# Zigbee.net
KiCad netlist of a schematic drawn in Altium Designer
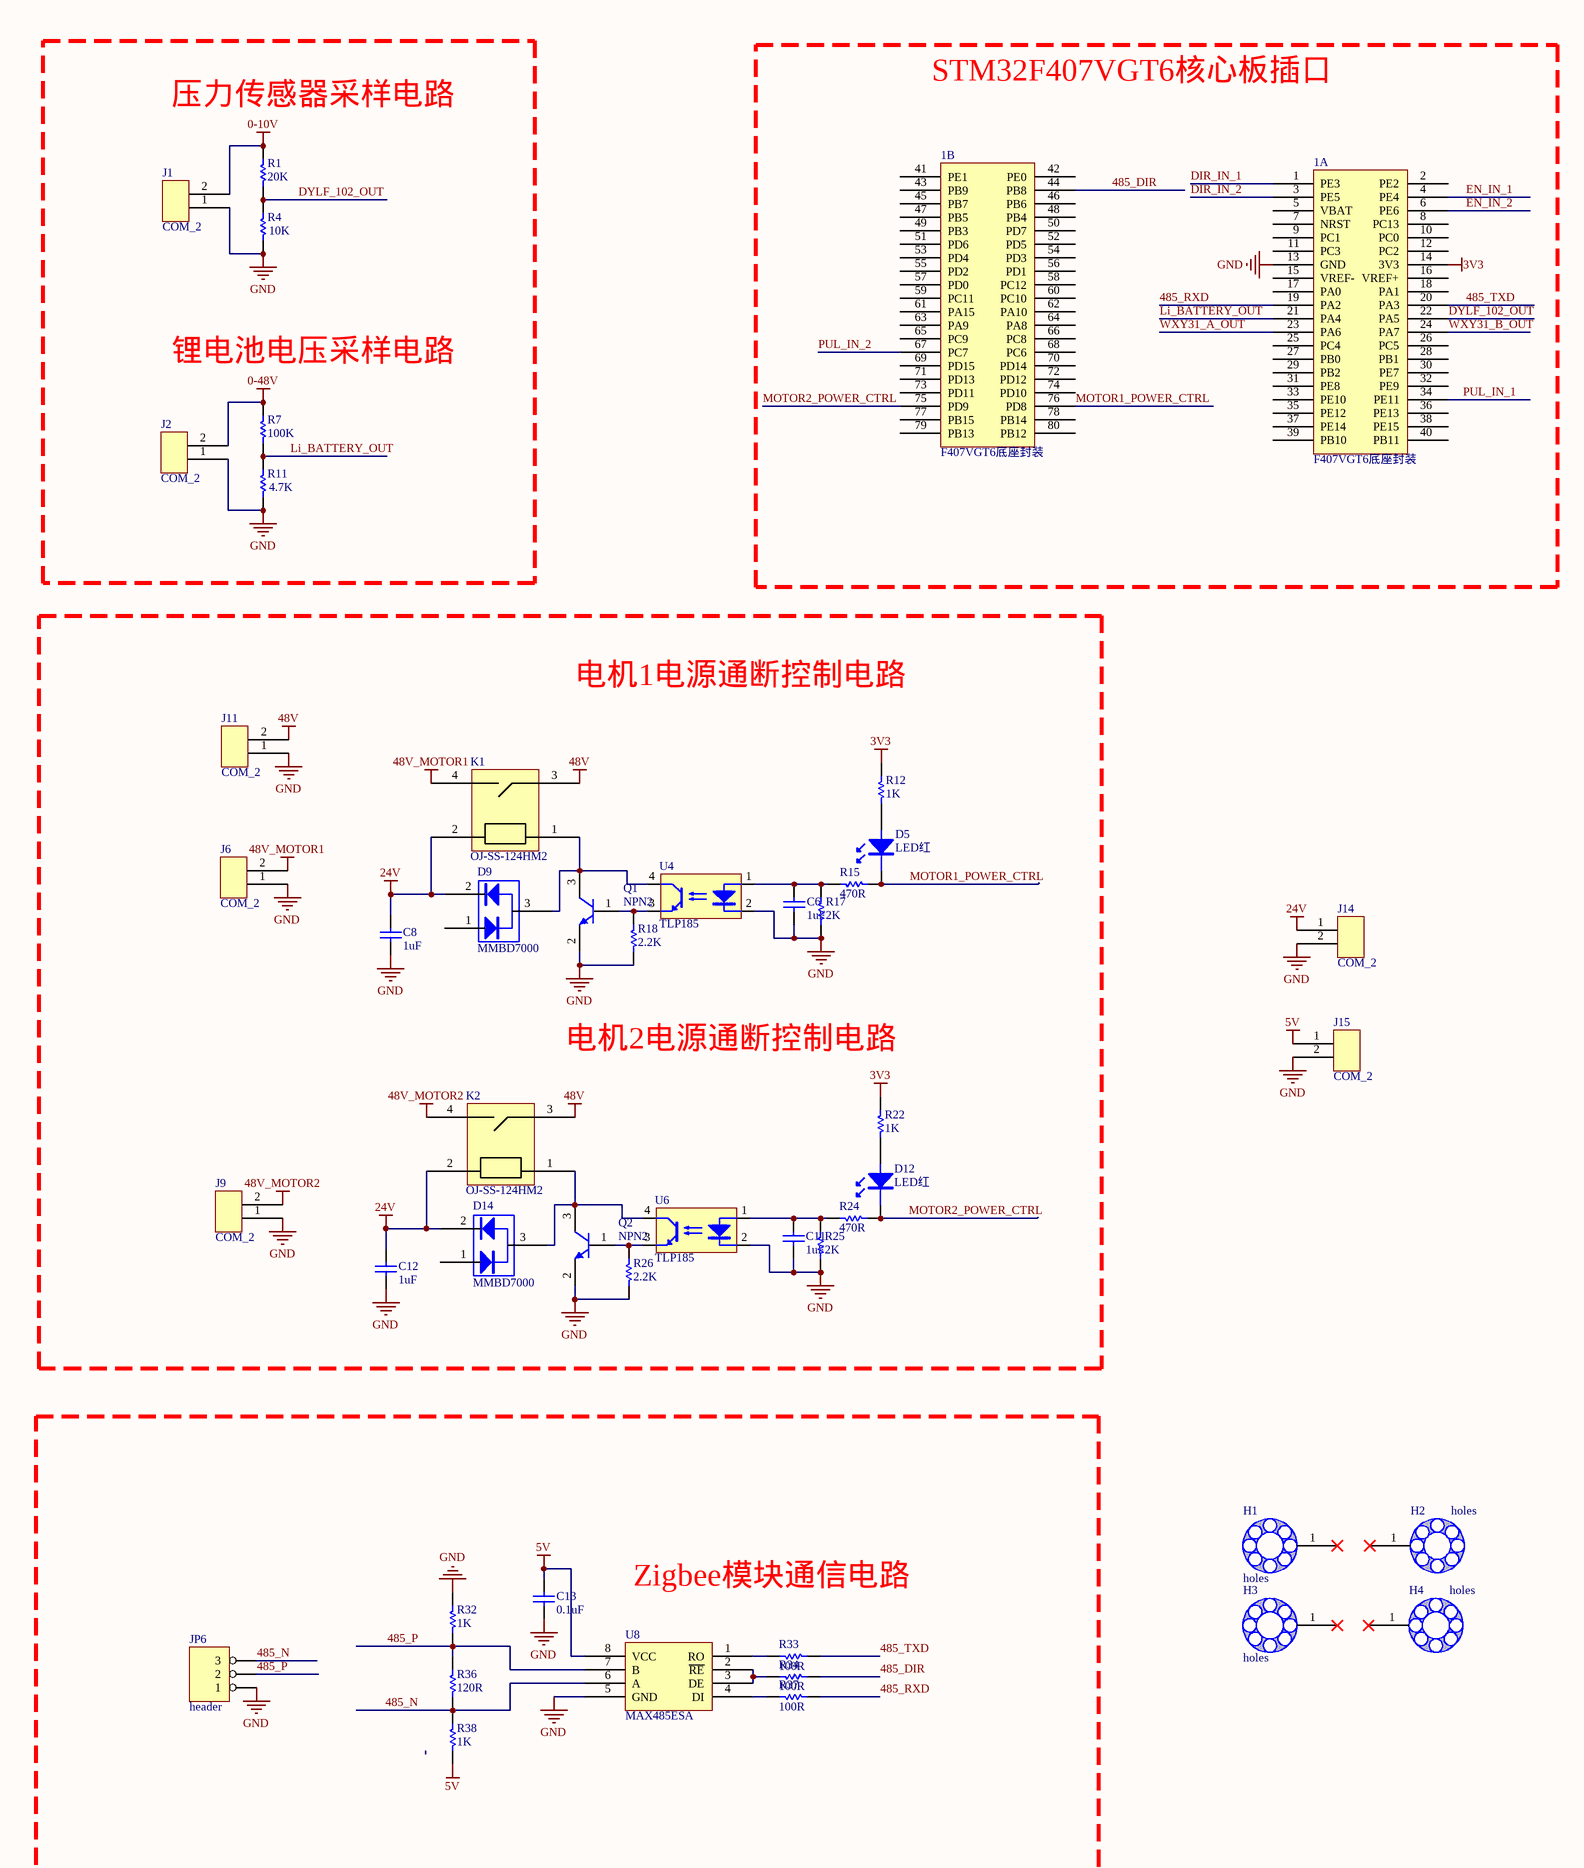
[diagram p0: Zigbee.SchDoc, left]
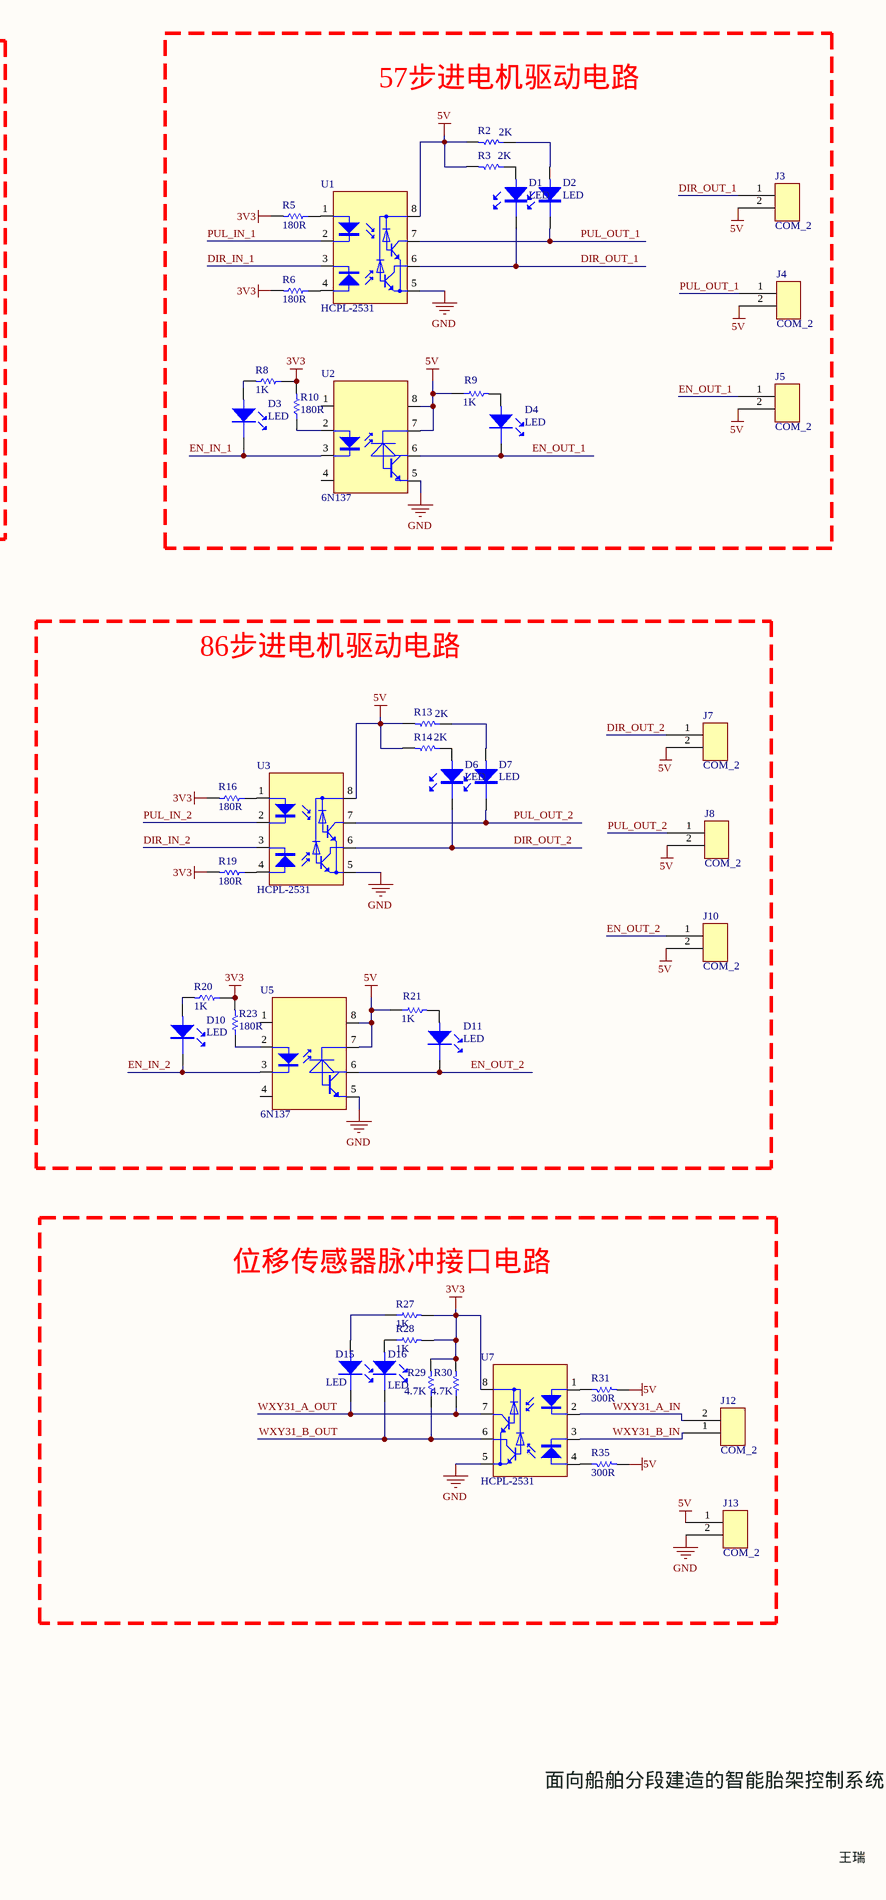
[diagram p1: Zigbee.SchDoc, right]

(export (version "E")
  (design (tool "Eeschema 10.0.6"))
  (components
    (comp (ref "1")
      (value "F407VGT6底座封装")
      (footprint "F407VGT6底座封装")
      (libsource (lib "F407VGT6底座封装") (part "F407VGT6底座封装"))
    )
    (comp (ref "C6")
      (value "1uF")
      (footprint "0603_C")
      (description "Capacitor")
      (fields (field (name "PUBLISHER") "Altium Limited"))
      (libsource (lib "My Footprint") (part "CAP"))
    )
    (comp (ref "C8")
      (value "1uF")
      (footprint "0603_C")
      (description "Capacitor")
      (fields (field (name "PUBLISHER") "Altium Limited"))
      (libsource (lib "My Footprint") (part "CAP"))
    )
    (comp (ref "C11")
      (value "1uF")
      (footprint "0603_C")
      (description "Capacitor")
      (fields (field (name "PUBLISHER") "Altium Limited"))
      (libsource (lib "My Footprint") (part "CAP"))
    )
    (comp (ref "C12")
      (value "1uF")
      (footprint "0603_C")
      (description "Capacitor")
      (fields (field (name "PUBLISHER") "Altium Limited"))
      (libsource (lib "My Footprint") (part "CAP"))
    )
    (comp (ref "C13")
      (value "0.1uF")
      (footprint "0603_C")
      (description "Capacitor")
      (fields (field (name "PUBLISHER") "Altium Limited"))
      (libsource (lib "My Footprint") (part "CAP"))
    )
    (comp (ref "D1")
      (value "LED")
      (footprint "0603_LED")
      (description "LED 发光二极管")
      (libsource (lib "My Footprint") (part "LED"))
    )
    (comp (ref "D2")
      (value "LED")
      (footprint "0603_LED")
      (description "LED 发光二极管")
      (libsource (lib "My Footprint") (part "LED"))
    )
    (comp (ref "D3")
      (value "LED")
      (footprint "0603_LED")
      (description "LED 发光二极管")
      (libsource (lib "My Footprint") (part "LED"))
    )
    (comp (ref "D4")
      (value "LED")
      (footprint "0603_LED")
      (description "LED 发光二极管")
      (libsource (lib "My Footprint") (part "LED"))
    )
    (comp (ref "D5")
      (value "LED红")
      (footprint "0603_LED")
      (description "LED 发光二极管")
      (libsource (lib "My Footprint") (part "LED"))
    )
    (comp (ref "D6")
      (value "LED")
      (footprint "0603_LED")
      (description "LED 发光二极管")
      (libsource (lib "My Footprint") (part "LED"))
    )
    (comp (ref "D7")
      (value "LED")
      (footprint "0603_LED")
      (description "LED 发光二极管")
      (libsource (lib "My Footprint") (part "LED"))
    )
    (comp (ref "D9") (value "MMBD7000") (footprint "SOT23") (libsource (lib "Footprint") (part "MMBD7000")))
    (comp (ref "D10")
      (value "LED")
      (footprint "0603_LED")
      (description "LED 发光二极管")
      (libsource (lib "My Footprint") (part "LED"))
    )
    (comp (ref "D11")
      (value "LED")
      (footprint "0603_LED")
      (description "LED 发光二极管")
      (libsource (lib "My Footprint") (part "LED"))
    )
    (comp (ref "D12")
      (value "LED红")
      (footprint "0603_LED")
      (description "LED 发光二极管")
      (libsource (lib "My Footprint") (part "LED"))
    )
    (comp (ref "D14") (value "MMBD7000") (footprint "SOT23") (libsource (lib "Footprint") (part "MMBD7000")))
    (comp (ref "D15")
      (value "LED")
      (footprint "0603_LED")
      (description "LED 发光二极管")
      (libsource (lib "My Footprint") (part "LED"))
    )
    (comp (ref "D16")
      (value "LED")
      (footprint "0603_LED")
      (description "LED 发光二极管")
      (libsource (lib "My Footprint") (part "LED"))
    )
    (comp (ref "H1") (value "holes") (footprint "铜柱（小焊盘）") (libsource (lib "Footprint") (part "铜柱")))
    (comp (ref "H2") (value "holes") (footprint "铜柱（小焊盘）") (libsource (lib "Footprint") (part "铜柱")))
    (comp (ref "H3") (value "holes") (footprint "铜柱（小焊盘）") (libsource (lib "Footprint") (part "铜柱")))
    (comp (ref "H4") (value "holes") (footprint "铜柱（小焊盘）") (libsource (lib "Footprint") (part "铜柱")))
    (comp (ref "J1") (value "COM_2") (footprint "5.08A-2PIN") (libsource (lib "") (part "COM_2_1")))
    (comp (ref "J2") (value "COM_2") (footprint "5.08A-2PIN") (libsource (lib "") (part "COM_2_1")))
    (comp (ref "J3") (value "COM_2") (footprint "5.08A-2PIN") (libsource (lib "Footprint") (part "COM_2")))
    (comp (ref "J4") (value "COM_2") (footprint "5.08A-2PIN") (libsource (lib "Footprint") (part "COM_2")))
    (comp (ref "J5") (value "COM_2") (footprint "5.08A-2PIN") (libsource (lib "Footprint") (part "COM_2")))
    (comp (ref "J6") (value "COM_2") (footprint "5.08A-2PIN") (libsource (lib "") (part "COM_2_1")))
    (comp (ref "J7") (value "COM_2") (footprint "5.08A-2PIN") (libsource (lib "Footprint") (part "COM_2")))
    (comp (ref "J8") (value "COM_2") (footprint "5.08A-2PIN") (libsource (lib "Footprint") (part "COM_2")))
    (comp (ref "J9") (value "COM_2") (footprint "5.08A-2PIN") (libsource (lib "") (part "COM_2_1")))
    (comp (ref "J10") (value "COM_2") (footprint "5.08A-2PIN") (libsource (lib "Footprint") (part "COM_2")))
    (comp (ref "J11") (value "COM_2") (footprint "5.08A-2PIN") (libsource (lib "") (part "COM_2_1")))
    (comp (ref "J12") (value "COM_2") (footprint "5.08A-2PIN") (libsource (lib "") (part "COM_2_2")))
    (comp (ref "J13") (value "COM_2") (footprint "5.08A-2PIN") (libsource (lib "Footprint") (part "COM_2")))
    (comp (ref "J14") (value "COM_2") (footprint "5.08A-2PIN") (libsource (lib "Footprint") (part "COM_2")))
    (comp (ref "J15") (value "COM_2") (footprint "5.08A-2PIN") (libsource (lib "Footprint") (part "COM_2")))
    (comp (ref "JP6")
      (value "header")
      (footprint "5.08A-3PIN")
      (libsource (lib "My Footprint") (part "HEADER 3"))
    )
    (comp (ref "K1")
      (value "OJ-SS-124HM2")
      (footprint "G4A-1A-PE-24V")
      (libsource (lib "Footprint") (part "OJ-SS-124HM2"))
    )
    (comp (ref "K2")
      (value "OJ-SS-124HM2")
      (footprint "G4A-1A-PE-24V")
      (libsource (lib "Footprint") (part "OJ-SS-124HM2"))
    )
    (comp (ref "Q1")
      (value "NPN2")
      (footprint "SOT-23-3")
      (description "贴片")
      (libsource (lib "My Footprint") (part "NPN2"))
    )
    (comp (ref "Q2")
      (value "NPN2")
      (footprint "SOT-23-3")
      (description "贴片")
      (libsource (lib "My Footprint") (part "NPN2"))
    )
    (comp (ref "R1")
      (value "20K")
      (footprint "0603_R")
      (description "Resistor")
      (fields (field (name "PUBLISHER") "Altium Limited"))
      (libsource (lib "My Footprint") (part "RES"))
    )
    (comp (ref "R2")
      (value "2K")
      (footprint "0603_R")
      (description "Resistor")
      (fields (field (name "PUBLISHER") "Altium Limited"))
      (libsource (lib "My Footprint") (part "RES"))
    )
    (comp (ref "R3")
      (value "2K")
      (footprint "0603_R")
      (description "Resistor")
      (fields (field (name "PUBLISHER") "Altium Limited"))
      (libsource (lib "My Footprint") (part "RES"))
    )
    (comp (ref "R4")
      (value "10K")
      (footprint "0603_R")
      (description "Resistor")
      (fields (field (name "PUBLISHER") "Altium Limited"))
      (libsource (lib "My Footprint") (part "RES"))
    )
    (comp (ref "R5")
      (value "180R")
      (footprint "0603_R")
      (description "Resistor")
      (fields (field (name "PUBLISHER") "Altium Limited"))
      (libsource (lib "My Footprint") (part "RES"))
    )
    (comp (ref "R6")
      (value "180R")
      (footprint "0603_R")
      (description "Resistor")
      (fields (field (name "PUBLISHER") "Altium Limited"))
      (libsource (lib "My Footprint") (part "RES"))
    )
    (comp (ref "R7")
      (value "100K")
      (footprint "0603_R")
      (description "Resistor")
      (fields (field (name "PUBLISHER") "Altium Limited"))
      (libsource (lib "My Footprint") (part "RES"))
    )
    (comp (ref "R8")
      (value "1K")
      (footprint "0603_R")
      (description "Resistor")
      (fields (field (name "PUBLISHER") "Altium Limited"))
      (libsource (lib "My Footprint") (part "RES"))
    )
    (comp (ref "R9")
      (value "1K")
      (footprint "0603_R")
      (description "Resistor")
      (fields (field (name "PUBLISHER") "Altium Limited"))
      (libsource (lib "My Footprint") (part "RES"))
    )
    (comp (ref "R10")
      (value "180R")
      (footprint "0603_R")
      (description "Resistor")
      (fields (field (name "PUBLISHER") "Altium Limited"))
      (libsource (lib "My Footprint") (part "RES"))
    )
    (comp (ref "R11")
      (value "4.7K")
      (footprint "0603_R")
      (description "Resistor")
      (fields (field (name "PUBLISHER") "Altium Limited"))
      (libsource (lib "My Footprint") (part "RES"))
    )
    (comp (ref "R12")
      (value "1K")
      (footprint "0603_R")
      (description "Resistor")
      (fields (field (name "PUBLISHER") "Altium Limited"))
      (libsource (lib "My Footprint") (part "RES"))
    )
    (comp (ref "R13")
      (value "2K")
      (footprint "0603_R")
      (description "Resistor")
      (fields (field (name "PUBLISHER") "Altium Limited"))
      (libsource (lib "My Footprint") (part "RES"))
    )
    (comp (ref "R14")
      (value "2K")
      (footprint "0603_R")
      (description "Resistor")
      (fields (field (name "PUBLISHER") "Altium Limited"))
      (libsource (lib "My Footprint") (part "RES"))
    )
    (comp (ref "R15")
      (value "470R")
      (footprint "0603_R")
      (description "Resistor")
      (fields (field (name "PUBLISHER") "Altium Limited"))
      (libsource (lib "My Footprint") (part "RES"))
    )
    (comp (ref "R16")
      (value "180R")
      (footprint "0603_R")
      (description "Resistor")
      (fields (field (name "PUBLISHER") "Altium Limited"))
      (libsource (lib "My Footprint") (part "RES"))
    )
    (comp (ref "R17")
      (value "2K")
      (footprint "0603_R")
      (description "Resistor")
      (fields (field (name "PUBLISHER") "Altium Limited"))
      (libsource (lib "My Footprint") (part "RES"))
    )
    (comp (ref "R18")
      (value "2.2K")
      (footprint "0603_R")
      (description "Resistor")
      (fields (field (name "PUBLISHER") "Altium Limited"))
      (libsource (lib "My Footprint") (part "RES"))
    )
    (comp (ref "R19")
      (value "180R")
      (footprint "0603_R")
      (description "Resistor")
      (fields (field (name "PUBLISHER") "Altium Limited"))
      (libsource (lib "My Footprint") (part "RES"))
    )
    (comp (ref "R20")
      (value "1K")
      (footprint "0603_R")
      (description "Resistor")
      (fields (field (name "PUBLISHER") "Altium Limited"))
      (libsource (lib "My Footprint") (part "RES"))
    )
    (comp (ref "R21")
      (value "1K")
      (footprint "0603_R")
      (description "Resistor")
      (fields (field (name "PUBLISHER") "Altium Limited"))
      (libsource (lib "My Footprint") (part "RES"))
    )
    (comp (ref "R22")
      (value "1K")
      (footprint "0603_R")
      (description "Resistor")
      (fields (field (name "PUBLISHER") "Altium Limited"))
      (libsource (lib "My Footprint") (part "RES"))
    )
    (comp (ref "R23")
      (value "180R")
      (footprint "0603_R")
      (description "Resistor")
      (fields (field (name "PUBLISHER") "Altium Limited"))
      (libsource (lib "My Footprint") (part "RES"))
    )
    (comp (ref "R24")
      (value "470R")
      (footprint "0603_R")
      (description "Resistor")
      (fields (field (name "PUBLISHER") "Altium Limited"))
      (libsource (lib "My Footprint") (part "RES"))
    )
    (comp (ref "R25")
      (value "2K")
      (footprint "0603_R")
      (description "Resistor")
      (fields (field (name "PUBLISHER") "Altium Limited"))
      (libsource (lib "My Footprint") (part "RES"))
    )
    (comp (ref "R26")
      (value "2.2K")
      (footprint "0603_R")
      (description "Resistor")
      (fields (field (name "PUBLISHER") "Altium Limited"))
      (libsource (lib "My Footprint") (part "RES"))
    )
    (comp (ref "R27")
      (value "1K")
      (footprint "0603_R")
      (description "Resistor")
      (fields (field (name "PUBLISHER") "Altium Limited"))
      (libsource (lib "My Footprint") (part "RES"))
    )
    (comp (ref "R28")
      (value "1K")
      (footprint "0603_R")
      (description "Resistor")
      (fields (field (name "PUBLISHER") "Altium Limited"))
      (libsource (lib "My Footprint") (part "RES"))
    )
    (comp (ref "R29")
      (value "4.7K")
      (footprint "0603_R")
      (description "Resistor")
      (fields (field (name "PUBLISHER") "Altium Limited"))
      (libsource (lib "My Footprint") (part "RES"))
    )
    (comp (ref "R30")
      (value "4.7K")
      (footprint "0603_R")
      (description "Resistor")
      (fields (field (name "PUBLISHER") "Altium Limited"))
      (libsource (lib "My Footprint") (part "RES"))
    )
    (comp (ref "R31")
      (value "300R")
      (footprint "0603_R")
      (description "Resistor")
      (fields (field (name "PUBLISHER") "Altium Limited"))
      (libsource (lib "My Footprint") (part "RES"))
    )
    (comp (ref "R32")
      (value "1K")
      (footprint "0603_R")
      (description "Resistor")
      (fields (field (name "PUBLISHER") "Altium Limited"))
      (libsource (lib "My Footprint") (part "RES"))
    )
    (comp (ref "R33")
      (value "100R")
      (footprint "0603_R")
      (description "Resistor")
      (fields (field (name "PUBLISHER") "Altium Limited"))
      (libsource (lib "My Footprint") (part "RES"))
    )
    (comp (ref "R34")
      (value "100R")
      (footprint "0603_R")
      (description "Resistor")
      (fields (field (name "PUBLISHER") "Altium Limited"))
      (libsource (lib "My Footprint") (part "RES"))
    )
    (comp (ref "R35")
      (value "300R")
      (footprint "0603_R")
      (description "Resistor")
      (fields (field (name "PUBLISHER") "Altium Limited"))
      (libsource (lib "My Footprint") (part "RES"))
    )
    (comp (ref "R36")
      (value "120R")
      (footprint "0603_R")
      (description "Resistor")
      (fields (field (name "PUBLISHER") "Altium Limited"))
      (libsource (lib "My Footprint") (part "RES"))
    )
    (comp (ref "R37")
      (value "100R")
      (footprint "0603_R")
      (description "Resistor")
      (fields (field (name "PUBLISHER") "Altium Limited"))
      (libsource (lib "My Footprint") (part "RES"))
    )
    (comp (ref "R38")
      (value "1K")
      (footprint "0603_R")
      (description "Resistor")
      (fields (field (name "PUBLISHER") "Altium Limited"))
      (libsource (lib "My Footprint") (part "RES"))
    )
    (comp (ref "U1") (value "HCPL-2531") (footprint "SOP8") (libsource (lib "LCD_CON") (part "HCPL-2531")))
    (comp (ref "U2") (value "6N137") (footprint "SOP8") (libsource (lib "LYT Devices") (part "6N137")))
    (comp (ref "U3") (value "HCPL-2531") (footprint "SOP8") (libsource (lib "LCD_CON") (part "HCPL-2531")))
    (comp (ref "U4") (value "TLP185") (footprint "SOP4") (libsource (lib "Footprint") (part "TLP184")))
    (comp (ref "U5") (value "6N137") (footprint "SOP8") (libsource (lib "LYT Devices") (part "6N137")))
    (comp (ref "U6") (value "TLP185") (footprint "SOP4") (libsource (lib "Footprint") (part "TLP184")))
    (comp (ref "U7") (value "HCPL-2531") (footprint "SOP8") (libsource (lib "LCD_CON") (part "HCPL-2531")))
    (comp (ref "U8") (value "MAX485ESA") (footprint "SOP8") (libsource (lib "Footprint") (part "MAX485ESA")))
  )
  (nets
    (net (code "1") (name "/485_DIR") (class "Default")
      (node (ref "1") (pin "44") (pinfunction "PB8_44") (pintype "passive"))
      (node (ref "R34") (pin "2") (pinfunction "2_2") (pintype "passive"))
    )
    (net (code "2") (name "/485_N") (class "Default")
      (node (ref "JP6") (pin "3") (pinfunction "3_3") (pintype "passive"))
      (node (ref "R36") (pin "1") (pinfunction "1_1") (pintype "passive"))
      (node (ref "R38") (pin "2") (pinfunction "2_2") (pintype "passive"))
      (node (ref "U8") (pin "6") (pinfunction "A_6") (pintype "power_in"))
    )
    (net (code "3") (name "/485_P") (class "Default")
      (node (ref "JP6") (pin "2") (pinfunction "2_2") (pintype "passive"))
      (node (ref "R32") (pin "1") (pinfunction "1_1") (pintype "passive"))
      (node (ref "R36") (pin "2") (pinfunction "2_2") (pintype "passive"))
      (node (ref "U8") (pin "7") (pinfunction "B_7") (pintype "power_in"))
    )
    (net (code "4") (name "/485_RXD") (class "Default")
      (node (ref "1") (pin "19") (pinfunction "PA2_19") (pintype "passive"))
      (node (ref "R37") (pin "2") (pinfunction "2_2") (pintype "passive"))
    )
    (net (code "5") (name "/485_TXD") (class "Default")
      (node (ref "1") (pin "20") (pinfunction "PA3_20") (pintype "passive"))
      (node (ref "R33") (pin "2") (pinfunction "2_2") (pintype "passive"))
    )
    (net (code "6") (name "/DIR_IN_1") (class "Default")
      (node (ref "1") (pin "1") (pinfunction "PE3_1") (pintype "passive"))
      (node (ref "U1") (pin "3") (pintype "passive"))
    )
    (net (code "7") (name "/DIR_IN_2") (class "Default")
      (node (ref "1") (pin "3") (pinfunction "PE5_3") (pintype "passive"))
      (node (ref "U3") (pin "3") (pintype "passive"))
    )
    (net (code "8") (name "/DIR_OUT_1") (class "Default")
      (node (ref "D1") (pin "2") (pinfunction "K_2") (pintype "passive"))
      (node (ref "J3") (pin "1") (pinfunction "1_1") (pintype "power_in"))
      (node (ref "U1") (pin "6") (pintype "passive"))
    )
    (net (code "9") (name "/DIR_OUT_2") (class "Default")
      (node (ref "D6") (pin "2") (pinfunction "K_2") (pintype "passive"))
      (node (ref "J7") (pin "1") (pinfunction "1_1") (pintype "power_in"))
      (node (ref "U3") (pin "6") (pintype "passive"))
    )
    (net (code "10") (name "/DYLF_102_OUT") (class "Default")
      (node (ref "1") (pin "22") (pinfunction "PA5_22") (pintype "passive"))
      (node (ref "R1") (pin "2") (pinfunction "2_2") (pintype "passive"))
      (node (ref "R4") (pin "1") (pinfunction "1_1") (pintype "passive"))
    )
    (net (code "11") (name "/EN_IN_1") (class "Default")
      (node (ref "1") (pin "4") (pinfunction "PE4_4") (pintype "passive"))
      (node (ref "D3") (pin "2") (pinfunction "K_2") (pintype "passive"))
      (node (ref "U2") (pin "3") (pintype "passive"))
    )
    (net (code "12") (name "/EN_IN_2") (class "Default")
      (node (ref "1") (pin "6") (pinfunction "PE6_6") (pintype "passive"))
      (node (ref "D10") (pin "2") (pinfunction "K_2") (pintype "passive"))
      (node (ref "U5") (pin "3") (pintype "passive"))
    )
    (net (code "13") (name "/EN_OUT_1") (class "Default")
      (node (ref "D4") (pin "2") (pinfunction "K_2") (pintype "passive"))
      (node (ref "J5") (pin "1") (pinfunction "1_1") (pintype "power_in"))
      (node (ref "U2") (pin "6") (pintype "passive"))
    )
    (net (code "14") (name "/EN_OUT_2") (class "Default")
      (node (ref "D11") (pin "2") (pinfunction "K_2") (pintype "passive"))
      (node (ref "J10") (pin "1") (pinfunction "1_1") (pintype "power_in"))
      (node (ref "U5") (pin "6") (pintype "passive"))
    )
    (net (code "15") (name "/Li_BATTERY_OUT") (class "Default")
      (node (ref "1") (pin "21") (pinfunction "PA4_21") (pintype "passive"))
      (node (ref "R11") (pin "1") (pinfunction "1_1") (pintype "passive"))
      (node (ref "R7") (pin "2") (pinfunction "2_2") (pintype "passive"))
    )
    (net (code "16") (name "/MOTOR1_POWER_CTRL") (class "Default")
      (node (ref "1") (pin "76") (pinfunction "PD8_76") (pintype "passive"))
      (node (ref "D5") (pin "2") (pinfunction "K_2") (pintype "passive"))
      (node (ref "R15") (pin "2") (pinfunction "2_2") (pintype "passive"))
    )
    (net (code "17") (name "/MOTOR2_POWER_CTRL") (class "Default")
      (node (ref "1") (pin "75") (pinfunction "PD9_75") (pintype "passive"))
      (node (ref "D12") (pin "2") (pinfunction "K_2") (pintype "passive"))
      (node (ref "R24") (pin "2") (pinfunction "2_2") (pintype "passive"))
    )
    (net (code "18") (name "/PUL_IN_1") (class "Default")
      (node (ref "1") (pin "34") (pinfunction "PE11_34") (pintype "passive"))
      (node (ref "U1") (pin "2") (pintype "passive"))
    )
    (net (code "19") (name "/PUL_IN_2") (class "Default")
      (node (ref "1") (pin "67") (pinfunction "PC7_67") (pintype "passive"))
      (node (ref "U3") (pin "2") (pintype "passive"))
    )
    (net (code "20") (name "/PUL_OUT_1") (class "Default")
      (node (ref "D2") (pin "2") (pinfunction "K_2") (pintype "passive"))
      (node (ref "J4") (pin "1") (pinfunction "1_1") (pintype "power_in"))
      (node (ref "U1") (pin "7") (pintype "passive"))
    )
    (net (code "21") (name "/PUL_OUT_2") (class "Default")
      (node (ref "D7") (pin "2") (pinfunction "K_2") (pintype "passive"))
      (node (ref "J8") (pin "1") (pinfunction "1_1") (pintype "power_in"))
      (node (ref "U3") (pin "7") (pintype "passive"))
    )
    (net (code "22") (name "/WXY31_A_IN") (class "Default")
      (node (ref "J12") (pin "2") (pinfunction "2_2") (pintype "power_in"))
      (node (ref "U7") (pin "2") (pintype "passive"))
    )
    (net (code "23") (name "/WXY31_A_OUT") (class "Default")
      (node (ref "1") (pin "23") (pinfunction "PA6_23") (pintype "passive"))
      (node (ref "D15") (pin "2") (pinfunction "K_2") (pintype "passive"))
      (node (ref "R30") (pin "1") (pinfunction "1_1") (pintype "passive"))
      (node (ref "U7") (pin "7") (pintype "passive"))
    )
    (net (code "24") (name "/WXY31_B_IN") (class "Default")
      (node (ref "J12") (pin "1") (pinfunction "1_1") (pintype "power_in"))
      (node (ref "U7") (pin "3") (pintype "passive"))
    )
    (net (code "25") (name "/WXY31_B_OUT") (class "Default")
      (node (ref "1") (pin "24") (pinfunction "PA7_24") (pintype "passive"))
      (node (ref "D16") (pin "2") (pinfunction "K_2") (pintype "passive"))
      (node (ref "R29") (pin "1") (pinfunction "1_1") (pintype "passive"))
      (node (ref "U7") (pin "6") (pintype "passive"))
    )
    (net (code "26") (name "0-10V") (class "Default")
      (node (ref "J1") (pin "2") (pinfunction "2_2") (pintype "power_in"))
      (node (ref "R1") (pin "1") (pinfunction "1_1") (pintype "passive"))
    )
    (net (code "27") (name "0-48V") (class "Default")
      (node (ref "J2") (pin "2") (pinfunction "2_2") (pintype "power_in"))
      (node (ref "R7") (pin "1") (pinfunction "1_1") (pintype "passive"))
    )
    (net (code "28") (name "3V3") (class "Default")
      (node (ref "1") (pin "14") (pinfunction "3V3_14") (pintype "passive"))
      (node (ref "R10") (pin "2") (pinfunction "2_2") (pintype "passive"))
      (node (ref "R12") (pin "2") (pinfunction "2_2") (pintype "passive"))
      (node (ref "R16") (pin "2") (pinfunction "2_2") (pintype "passive"))
      (node (ref "R19") (pin "2") (pinfunction "2_2") (pintype "passive"))
      (node (ref "R20") (pin "1") (pinfunction "1_1") (pintype "passive"))
      (node (ref "R22") (pin "2") (pinfunction "2_2") (pintype "passive"))
      (node (ref "R23") (pin "2") (pinfunction "2_2") (pintype "passive"))
      (node (ref "R27") (pin "2") (pinfunction "2_2") (pintype "passive"))
      (node (ref "R28") (pin "2") (pinfunction "2_2") (pintype "passive"))
      (node (ref "R29") (pin "2") (pinfunction "2_2") (pintype "passive"))
      (node (ref "R30") (pin "2") (pinfunction "2_2") (pintype "passive"))
      (node (ref "R5") (pin "2") (pinfunction "2_2") (pintype "passive"))
      (node (ref "R6") (pin "2") (pinfunction "2_2") (pintype "passive"))
      (node (ref "R8") (pin "1") (pinfunction "1_1") (pintype "passive"))
      (node (ref "U7") (pin "8") (pintype "passive"))
    )
    (net (code "29") (name "5V") (class "Default")
      (node (ref "C13") (pin "2") (pinfunction "2_2") (pintype "passive"))
      (node (ref "J10") (pin "2") (pinfunction "2_2") (pintype "power_in"))
      (node (ref "J13") (pin "1") (pinfunction "1_1") (pintype "power_in"))
      (node (ref "J15") (pin "1") (pinfunction "1_1") (pintype "power_in"))
      (node (ref "J3") (pin "2") (pinfunction "2_2") (pintype "power_in"))
      (node (ref "J4") (pin "2") (pinfunction "2_2") (pintype "power_in"))
      (node (ref "J5") (pin "2") (pinfunction "2_2") (pintype "power_in"))
      (node (ref "J7") (pin "2") (pinfunction "2_2") (pintype "power_in"))
      (node (ref "J8") (pin "2") (pinfunction "2_2") (pintype "power_in"))
      (node (ref "R13") (pin "2") (pinfunction "2_2") (pintype "passive"))
      (node (ref "R14") (pin "2") (pinfunction "2_2") (pintype "passive"))
      (node (ref "R2") (pin "2") (pinfunction "2_2") (pintype "passive"))
      (node (ref "R21") (pin "1") (pinfunction "1_1") (pintype "passive"))
      (node (ref "R3") (pin "2") (pinfunction "2_2") (pintype "passive"))
      (node (ref "R31") (pin "2") (pinfunction "2_2") (pintype "passive"))
      (node (ref "R35") (pin "2") (pinfunction "2_2") (pintype "passive"))
      (node (ref "R38") (pin "1") (pinfunction "1_1") (pintype "passive"))
      (node (ref "R9") (pin "1") (pinfunction "1_1") (pintype "passive"))
      (node (ref "U1") (pin "8") (pintype "passive"))
      (node (ref "U2") (pin "7") (pintype "passive"))
      (node (ref "U2") (pin "8") (pintype "passive"))
      (node (ref "U3") (pin "8") (pintype "passive"))
      (node (ref "U5") (pin "7") (pintype "passive"))
      (node (ref "U5") (pin "8") (pintype "passive"))
      (node (ref "U8") (pin "8") (pinfunction "VCC_8") (pintype "power_in"))
    )
    (net (code "30") (name "24V") (class "Default")
      (node (ref "C12") (pin "2") (pinfunction "2_2") (pintype "passive"))
      (node (ref "C8") (pin "2") (pinfunction "2_2") (pintype "passive"))
      (node (ref "D14") (pin "2") (pinfunction "2_2") (pintype "passive"))
      (node (ref "D9") (pin "2") (pinfunction "2_2") (pintype "passive"))
      (node (ref "J14") (pin "1") (pinfunction "1_1") (pintype "power_in"))
      (node (ref "K1") (pin "2") (pinfunction "2_2") (pintype "power_in"))
      (node (ref "K2") (pin "2") (pinfunction "2_2") (pintype "power_in"))
    )
    (net (code "31") (name "48V") (class "Default")
      (node (ref "J11") (pin "2") (pinfunction "2_2") (pintype "power_in"))
      (node (ref "K1") (pin "3") (pinfunction "3_3") (pintype "power_in"))
      (node (ref "K2") (pin "3") (pinfunction "3_3") (pintype "power_in"))
    )
    (net (code "32") (name "48V_MOTOR1") (class "Default")
      (node (ref "J6") (pin "2") (pinfunction "2_2") (pintype "power_in"))
      (node (ref "K1") (pin "4") (pinfunction "4_4") (pintype "power_in"))
    )
    (net (code "33") (name "48V_MOTOR2") (class "Default")
      (node (ref "J9") (pin "2") (pinfunction "2_2") (pintype "power_in"))
      (node (ref "K2") (pin "4") (pinfunction "4_4") (pintype "power_in"))
    )
    (net (code "34") (name "GND") (class "Default")
      (node (ref "1") (pin "13") (pinfunction "GND_13") (pintype "passive"))
      (node (ref "C11") (pin "2") (pinfunction "2_2") (pintype "passive"))
      (node (ref "C12") (pin "1") (pinfunction "1_1") (pintype "passive"))
      (node (ref "C13") (pin "1") (pinfunction "1_1") (pintype "passive"))
      (node (ref "C6") (pin "2") (pinfunction "2_2") (pintype "passive"))
      (node (ref "C8") (pin "1") (pinfunction "1_1") (pintype "passive"))
      (node (ref "J1") (pin "1") (pinfunction "1_1") (pintype "power_in"))
      (node (ref "J11") (pin "1") (pinfunction "1_1") (pintype "power_in"))
      (node (ref "J13") (pin "2") (pinfunction "2_2") (pintype "power_in"))
      (node (ref "J14") (pin "2") (pinfunction "2_2") (pintype "power_in"))
      (node (ref "J15") (pin "2") (pinfunction "2_2") (pintype "power_in"))
      (node (ref "J2") (pin "1") (pinfunction "1_1") (pintype "power_in"))
      (node (ref "J6") (pin "1") (pinfunction "1_1") (pintype "power_in"))
      (node (ref "J9") (pin "1") (pinfunction "1_1") (pintype "power_in"))
      (node (ref "JP6") (pin "1") (pinfunction "1_1") (pintype "passive"))
      (node (ref "Q1") (pin "2") (pinfunction "E_2") (pintype "passive"))
      (node (ref "Q2") (pin "2") (pinfunction "E_2") (pintype "passive"))
      (node (ref "R11") (pin "2") (pinfunction "2_2") (pintype "passive"))
      (node (ref "R17") (pin "2") (pinfunction "2_2") (pintype "passive"))
      (node (ref "R18") (pin "2") (pinfunction "2_2") (pintype "passive"))
      (node (ref "R25") (pin "2") (pinfunction "2_2") (pintype "passive"))
      (node (ref "R26") (pin "2") (pinfunction "2_2") (pintype "passive"))
      (node (ref "R32") (pin "2") (pinfunction "2_2") (pintype "passive"))
      (node (ref "R4") (pin "2") (pinfunction "2_2") (pintype "passive"))
      (node (ref "U1") (pin "5") (pintype "passive"))
      (node (ref "U2") (pin "5") (pintype "passive"))
      (node (ref "U3") (pin "5") (pintype "passive"))
      (node (ref "U4") (pin "2") (pinfunction "2_2") (pintype "passive"))
      (node (ref "U5") (pin "5") (pintype "passive"))
      (node (ref "U6") (pin "2") (pinfunction "2_2") (pintype "passive"))
      (node (ref "U7") (pin "5") (pintype "passive"))
      (node (ref "U8") (pin "5") (pinfunction "GND_5") (pintype "power_in"))
    )
    (net (code "35") (name "Net-(C6-Pad1)") (class "Default")
      (node (ref "C6") (pin "1") (pinfunction "1_1") (pintype "passive"))
      (node (ref "R15") (pin "1") (pinfunction "1_1") (pintype "passive"))
      (node (ref "R17") (pin "1") (pinfunction "1_1") (pintype "passive"))
      (node (ref "U4") (pin "1") (pinfunction "1_1") (pintype "passive"))
    )
    (net (code "36") (name "Net-(C11-Pad1)") (class "Default")
      (node (ref "C11") (pin "1") (pinfunction "1_1") (pintype "passive"))
      (node (ref "R24") (pin "1") (pinfunction "1_1") (pintype "passive"))
      (node (ref "R25") (pin "1") (pinfunction "1_1") (pintype "passive"))
      (node (ref "U6") (pin "1") (pinfunction "1_1") (pintype "passive"))
    )
    (net (code "37") (name "Net-(D1-A)") (class "Default")
      (node (ref "D1") (pin "1") (pinfunction "A_1") (pintype "passive"))
      (node (ref "R3") (pin "1") (pinfunction "1_1") (pintype "passive"))
    )
    (net (code "38") (name "Net-(D2-A)") (class "Default")
      (node (ref "D2") (pin "1") (pinfunction "A_1") (pintype "passive"))
      (node (ref "R2") (pin "1") (pinfunction "1_1") (pintype "passive"))
    )
    (net (code "39") (name "Net-(D3-A)") (class "Default")
      (node (ref "D3") (pin "1") (pinfunction "A_1") (pintype "passive"))
      (node (ref "R8") (pin "2") (pinfunction "2_2") (pintype "passive"))
    )
    (net (code "40") (name "Net-(D4-A)") (class "Default")
      (node (ref "D4") (pin "1") (pinfunction "A_1") (pintype "passive"))
      (node (ref "R9") (pin "2") (pinfunction "2_2") (pintype "passive"))
    )
    (net (code "41") (name "Net-(D5-A)") (class "Default")
      (node (ref "D5") (pin "1") (pinfunction "A_1") (pintype "passive"))
      (node (ref "R12") (pin "1") (pinfunction "1_1") (pintype "passive"))
    )
    (net (code "42") (name "Net-(D6-A)") (class "Default")
      (node (ref "D6") (pin "1") (pinfunction "A_1") (pintype "passive"))
      (node (ref "R14") (pin "1") (pinfunction "1_1") (pintype "passive"))
    )
    (net (code "43") (name "Net-(D7-A)") (class "Default")
      (node (ref "D7") (pin "1") (pinfunction "A_1") (pintype "passive"))
      (node (ref "R13") (pin "1") (pinfunction "1_1") (pintype "passive"))
    )
    (net (code "44") (name "Net-(D10-A)") (class "Default")
      (node (ref "D10") (pin "1") (pinfunction "A_1") (pintype "passive"))
      (node (ref "R20") (pin "2") (pinfunction "2_2") (pintype "passive"))
    )
    (net (code "45") (name "Net-(D11-A)") (class "Default")
      (node (ref "D11") (pin "1") (pinfunction "A_1") (pintype "passive"))
      (node (ref "R21") (pin "2") (pinfunction "2_2") (pintype "passive"))
    )
    (net (code "46") (name "Net-(D12-A)") (class "Default")
      (node (ref "D12") (pin "1") (pinfunction "A_1") (pintype "passive"))
      (node (ref "R22") (pin "1") (pinfunction "1_1") (pintype "passive"))
    )
    (net (code "47") (name "Net-(D15-A)") (class "Default")
      (node (ref "D15") (pin "1") (pinfunction "A_1") (pintype "passive"))
      (node (ref "R27") (pin "1") (pinfunction "1_1") (pintype "passive"))
    )
    (net (code "48") (name "Net-(D16-A)") (class "Default")
      (node (ref "D16") (pin "1") (pinfunction "A_1") (pintype "passive"))
      (node (ref "R28") (pin "1") (pinfunction "1_1") (pintype "passive"))
    )
    (net (code "49") (name "Net-(Q1-B)") (class "Default")
      (node (ref "Q1") (pin "1") (pinfunction "B_1") (pintype "passive"))
      (node (ref "R18") (pin "1") (pinfunction "1_1") (pintype "passive"))
      (node (ref "U4") (pin "3") (pinfunction "3_3") (pintype "passive"))
    )
    (net (code "50") (name "Net-(Q1-C)") (class "Default")
      (node (ref "D9") (pin "3") (pinfunction "3_3") (pintype "passive"))
      (node (ref "K1") (pin "1") (pinfunction "1_1") (pintype "power_in"))
      (node (ref "Q1") (pin "3") (pinfunction "C_3") (pintype "passive"))
      (node (ref "U4") (pin "4") (pinfunction "4_4") (pintype "passive"))
    )
    (net (code "51") (name "Net-(Q2-B)") (class "Default")
      (node (ref "Q2") (pin "1") (pinfunction "B_1") (pintype "passive"))
      (node (ref "R26") (pin "1") (pinfunction "1_1") (pintype "passive"))
      (node (ref "U6") (pin "3") (pinfunction "3_3") (pintype "passive"))
    )
    (net (code "52") (name "Net-(Q2-C)") (class "Default")
      (node (ref "D14") (pin "3") (pinfunction "3_3") (pintype "passive"))
      (node (ref "K2") (pin "1") (pinfunction "1_1") (pintype "power_in"))
      (node (ref "Q2") (pin "3") (pinfunction "C_3") (pintype "passive"))
      (node (ref "U6") (pin "4") (pinfunction "4_4") (pintype "passive"))
    )
    (net (code "53") (name "Net-(R5-Pad1)") (class "Default")
      (node (ref "R5") (pin "1") (pinfunction "1_1") (pintype "passive"))
      (node (ref "U1") (pin "1") (pintype "passive"))
    )
    (net (code "54") (name "Net-(R6-Pad1)") (class "Default")
      (node (ref "R6") (pin "1") (pinfunction "1_1") (pintype "passive"))
      (node (ref "U1") (pin "4") (pintype "passive"))
    )
    (net (code "55") (name "Net-(R10-Pad1)") (class "Default")
      (node (ref "R10") (pin "1") (pinfunction "1_1") (pintype "passive"))
      (node (ref "U2") (pin "2") (pintype "passive"))
    )
    (net (code "56") (name "Net-(R16-Pad1)") (class "Default")
      (node (ref "R16") (pin "1") (pinfunction "1_1") (pintype "passive"))
      (node (ref "U3") (pin "1") (pintype "passive"))
    )
    (net (code "57") (name "Net-(R19-Pad1)") (class "Default")
      (node (ref "R19") (pin "1") (pinfunction "1_1") (pintype "passive"))
      (node (ref "U3") (pin "4") (pintype "passive"))
    )
    (net (code "58") (name "Net-(R23-Pad1)") (class "Default")
      (node (ref "R23") (pin "1") (pinfunction "1_1") (pintype "passive"))
      (node (ref "U5") (pin "2") (pintype "passive"))
    )
    (net (code "59") (name "Net-(R31-Pad1)") (class "Default")
      (node (ref "R31") (pin "1") (pinfunction "1_1") (pintype "passive"))
      (node (ref "U7") (pin "1") (pintype "passive"))
    )
    (net (code "60") (name "Net-(R35-Pad1)") (class "Default")
      (node (ref "R35") (pin "1") (pinfunction "1_1") (pintype "passive"))
      (node (ref "U7") (pin "4") (pintype "passive"))
    )
    (net (code "61") (name "Net-(U8-DE)") (class "Default")
      (node (ref "R34") (pin "1") (pinfunction "1_1") (pintype "passive"))
      (node (ref "U8") (pin "2") (pinfunction "~{RE}_2") (pintype "power_in"))
      (node (ref "U8") (pin "3") (pinfunction "DE_3") (pintype "power_in"))
    )
    (net (code "62") (name "Net-(U8-DI)") (class "Default")
      (node (ref "R37") (pin "1") (pinfunction "1_1") (pintype "passive"))
      (node (ref "U8") (pin "4") (pinfunction "DI_4") (pintype "power_in"))
    )
    (net (code "63") (name "Net-(U8-RO)") (class "Default")
      (node (ref "R33") (pin "1") (pinfunction "1_1") (pintype "passive"))
      (node (ref "U8") (pin "1") (pinfunction "RO_1") (pintype "power_in"))
    )
    (net (code "64") (name "unconnected-(1A-NRST-Pad7)") (class "Default")
      (node (ref "1") (pin "7") (pinfunction "NRST_7") (pintype "passive"))
    )
    (net (code "65") (name "unconnected-(1A-PA0-Pad17)") (class "Default")
      (node (ref "1") (pin "17") (pinfunction "PA0_17") (pintype "passive"))
    )
    (net (code "66") (name "unconnected-(1A-PA1-Pad18)") (class "Default")
      (node (ref "1") (pin "18") (pinfunction "PA1_18") (pintype "passive"))
    )
    (net (code "67") (name "unconnected-(1A-PB0-Pad27)") (class "Default")
      (node (ref "1") (pin "27") (pinfunction "PB0_27") (pintype "passive"))
    )
    (net (code "68") (name "unconnected-(1A-PB1-Pad28)") (class "Default")
      (node (ref "1") (pin "28") (pinfunction "PB1_28") (pintype "passive"))
    )
    (net (code "69") (name "unconnected-(1A-PB2-Pad29)") (class "Default")
      (node (ref "1") (pin "29") (pinfunction "PB2_29") (pintype "passive"))
    )
    (net (code "70") (name "unconnected-(1A-PB10-Pad39)") (class "Default")
      (node (ref "1") (pin "39") (pinfunction "PB10_39") (pintype "passive"))
    )
    (net (code "71") (name "unconnected-(1A-PB11-Pad40)") (class "Default")
      (node (ref "1") (pin "40") (pinfunction "PB11_40") (pintype "passive"))
    )
    (net (code "72") (name "unconnected-(1A-PC0-Pad10)") (class "Default")
      (node (ref "1") (pin "10") (pinfunction "PC0_10") (pintype "passive"))
    )
    (net (code "73") (name "unconnected-(1A-PC1-Pad9)") (class "Default")
      (node (ref "1") (pin "9") (pinfunction "PC1_9") (pintype "passive"))
    )
    (net (code "74") (name "unconnected-(1A-PC2-Pad12)") (class "Default")
      (node (ref "1") (pin "12") (pinfunction "PC2_12") (pintype "passive"))
    )
    (net (code "75") (name "unconnected-(1A-PC3-Pad11)") (class "Default")
      (node (ref "1") (pin "11") (pinfunction "PC3_11") (pintype "passive"))
    )
    (net (code "76") (name "unconnected-(1A-PC4-Pad25)") (class "Default")
      (node (ref "1") (pin "25") (pinfunction "PC4_25") (pintype "passive"))
    )
    (net (code "77") (name "unconnected-(1A-PC5-Pad26)") (class "Default")
      (node (ref "1") (pin "26") (pinfunction "PC5_26") (pintype "passive"))
    )
    (net (code "78") (name "unconnected-(1A-PC13-Pad8)") (class "Default")
      (node (ref "1") (pin "8") (pinfunction "PC13_8") (pintype "passive"))
    )
    (net (code "79") (name "unconnected-(1A-PE2-Pad2)") (class "Default")
      (node (ref "1") (pin "2") (pinfunction "PE2_2") (pintype "passive"))
    )
    (net (code "80") (name "unconnected-(1A-PE7-Pad30)") (class "Default")
      (node (ref "1") (pin "30") (pinfunction "PE7_30") (pintype "passive"))
    )
    (net (code "81") (name "unconnected-(1A-PE8-Pad31)") (class "Default")
      (node (ref "1") (pin "31") (pinfunction "PE8_31") (pintype "passive"))
    )
    (net (code "82") (name "unconnected-(1A-PE9-Pad32)") (class "Default")
      (node (ref "1") (pin "32") (pinfunction "PE9_32") (pintype "passive"))
    )
    (net (code "83") (name "unconnected-(1A-PE10-Pad33)") (class "Default")
      (node (ref "1") (pin "33") (pinfunction "PE10_33") (pintype "passive"))
    )
    (net (code "84") (name "unconnected-(1A-PE12-Pad35)") (class "Default")
      (node (ref "1") (pin "35") (pinfunction "PE12_35") (pintype "passive"))
    )
    (net (code "85") (name "unconnected-(1A-PE13-Pad36)") (class "Default")
      (node (ref "1") (pin "36") (pinfunction "PE13_36") (pintype "passive"))
    )
    (net (code "86") (name "unconnected-(1A-PE14-Pad37)") (class "Default")
      (node (ref "1") (pin "37") (pinfunction "PE14_37") (pintype "passive"))
    )
    (net (code "87") (name "unconnected-(1A-PE15-Pad38)") (class "Default")
      (node (ref "1") (pin "38") (pinfunction "PE15_38") (pintype "passive"))
    )
    (net (code "88") (name "unconnected-(1A-VBAT-Pad5)") (class "Default")
      (node (ref "1") (pin "5") (pinfunction "VBAT_5") (pintype "passive"))
    )
    (net (code "89") (name "unconnected-(1A-VREF+-Pad16)") (class "Default")
      (node (ref "1") (pin "16") (pinfunction "VREF+_16") (pintype "passive"))
    )
    (net (code "90") (name "unconnected-(1A-VREF--Pad15)") (class "Default")
      (node (ref "1") (pin "15") (pinfunction "VREF-_15") (pintype "passive"))
    )
    (net (code "91") (name "unconnected-(1B-PA8-Pad64)") (class "Default")
      (node (ref "1") (pin "64") (pinfunction "PA8_64") (pintype "passive"))
    )
    (net (code "92") (name "unconnected-(1B-PA9-Pad63)") (class "Default")
      (node (ref "1") (pin "63") (pinfunction "PA9_63") (pintype "passive"))
    )
    (net (code "93") (name "unconnected-(1B-PA10-Pad62)") (class "Default")
      (node (ref "1") (pin "62") (pinfunction "PA10_62") (pintype "passive"))
    )
    (net (code "94") (name "unconnected-(1B-PA15-Pad61)") (class "Default")
      (node (ref "1") (pin "61") (pinfunction "PA15_61") (pintype "passive"))
    )
    (net (code "95") (name "unconnected-(1B-PB3-Pad49)") (class "Default")
      (node (ref "1") (pin "49") (pinfunction "PB3_49") (pintype "passive"))
    )
    (net (code "96") (name "unconnected-(1B-PB4-Pad48)") (class "Default")
      (node (ref "1") (pin "48") (pinfunction "PB4_48") (pintype "passive"))
    )
    (net (code "97") (name "unconnected-(1B-PB5-Pad47)") (class "Default")
      (node (ref "1") (pin "47") (pinfunction "PB5_47") (pintype "passive"))
    )
    (net (code "98") (name "unconnected-(1B-PB6-Pad46)") (class "Default")
      (node (ref "1") (pin "46") (pinfunction "PB6_46") (pintype "passive"))
    )
    (net (code "99") (name "unconnected-(1B-PB7-Pad45)") (class "Default")
      (node (ref "1") (pin "45") (pinfunction "PB7_45") (pintype "passive"))
    )
    (net (code "100") (name "unconnected-(1B-PB9-Pad43)") (class "Default")
      (node (ref "1") (pin "43") (pinfunction "PB9_43") (pintype "passive"))
    )
    (net (code "101") (name "unconnected-(1B-PB12-Pad80)") (class "Default")
      (node (ref "1") (pin "80") (pinfunction "PB12_80") (pintype "passive"))
    )
    (net (code "102") (name "unconnected-(1B-PB13-Pad79)") (class "Default")
      (node (ref "1") (pin "79") (pinfunction "PB13_79") (pintype "passive"))
    )
    (net (code "103") (name "unconnected-(1B-PB14-Pad78)") (class "Default")
      (node (ref "1") (pin "78") (pinfunction "PB14_78") (pintype "passive"))
    )
    (net (code "104") (name "unconnected-(1B-PB15-Pad77)") (class "Default")
      (node (ref "1") (pin "77") (pinfunction "PB15_77") (pintype "passive"))
    )
    (net (code "105") (name "unconnected-(1B-PC6-Pad68)") (class "Default")
      (node (ref "1") (pin "68") (pinfunction "PC6_68") (pintype "passive"))
    )
    (net (code "106") (name "unconnected-(1B-PC8-Pad66)") (class "Default")
      (node (ref "1") (pin "66") (pinfunction "PC8_66") (pintype "passive"))
    )
    (net (code "107") (name "unconnected-(1B-PC9-Pad65)") (class "Default")
      (node (ref "1") (pin "65") (pinfunction "PC9_65") (pintype "passive"))
    )
    (net (code "108") (name "unconnected-(1B-PC10-Pad60)") (class "Default")
      (node (ref "1") (pin "60") (pinfunction "PC10_60") (pintype "passive"))
    )
    (net (code "109") (name "unconnected-(1B-PC11-Pad59)") (class "Default")
      (node (ref "1") (pin "59") (pinfunction "PC11_59") (pintype "passive"))
    )
    (net (code "110") (name "unconnected-(1B-PC12-Pad58)") (class "Default")
      (node (ref "1") (pin "58") (pinfunction "PC12_58") (pintype "passive"))
    )
    (net (code "111") (name "unconnected-(1B-PD0-Pad57)") (class "Default")
      (node (ref "1") (pin "57") (pinfunction "PD0_57") (pintype "passive"))
    )
    (net (code "112") (name "unconnected-(1B-PD1-Pad56)") (class "Default")
      (node (ref "1") (pin "56") (pinfunction "PD1_56") (pintype "passive"))
    )
    (net (code "113") (name "unconnected-(1B-PD2-Pad55)") (class "Default")
      (node (ref "1") (pin "55") (pinfunction "PD2_55") (pintype "passive"))
    )
    (net (code "114") (name "unconnected-(1B-PD3-Pad54)") (class "Default")
      (node (ref "1") (pin "54") (pinfunction "PD3_54") (pintype "passive"))
    )
    (net (code "115") (name "unconnected-(1B-PD4-Pad53)") (class "Default")
      (node (ref "1") (pin "53") (pinfunction "PD4_53") (pintype "passive"))
    )
    (net (code "116") (name "unconnected-(1B-PD5-Pad52)") (class "Default")
      (node (ref "1") (pin "52") (pinfunction "PD5_52") (pintype "passive"))
    )
    (net (code "117") (name "unconnected-(1B-PD6-Pad51)") (class "Default")
      (node (ref "1") (pin "51") (pinfunction "PD6_51") (pintype "passive"))
    )
    (net (code "118") (name "unconnected-(1B-PD7-Pad50)") (class "Default")
      (node (ref "1") (pin "50") (pinfunction "PD7_50") (pintype "passive"))
    )
    (net (code "119") (name "unconnected-(1B-PD10-Pad74)") (class "Default")
      (node (ref "1") (pin "74") (pinfunction "PD10_74") (pintype "passive"))
    )
    (net (code "120") (name "unconnected-(1B-PD11-Pad73)") (class "Default")
      (node (ref "1") (pin "73") (pinfunction "PD11_73") (pintype "passive"))
    )
    (net (code "121") (name "unconnected-(1B-PD12-Pad72)") (class "Default")
      (node (ref "1") (pin "72") (pinfunction "PD12_72") (pintype "passive"))
    )
    (net (code "122") (name "unconnected-(1B-PD13-Pad71)") (class "Default")
      (node (ref "1") (pin "71") (pinfunction "PD13_71") (pintype "passive"))
    )
    (net (code "123") (name "unconnected-(1B-PD14-Pad70)") (class "Default")
      (node (ref "1") (pin "70") (pinfunction "PD14_70") (pintype "passive"))
    )
    (net (code "124") (name "unconnected-(1B-PD15-Pad69)") (class "Default")
      (node (ref "1") (pin "69") (pinfunction "PD15_69") (pintype "passive"))
    )
    (net (code "125") (name "unconnected-(1B-PE0-Pad42)") (class "Default")
      (node (ref "1") (pin "42") (pinfunction "PE0_42") (pintype "passive"))
    )
    (net (code "126") (name "unconnected-(1B-PE1-Pad41)") (class "Default")
      (node (ref "1") (pin "41") (pinfunction "PE1_41") (pintype "passive"))
    )
    (net (code "127") (name "unconnected-(D9-Pad1)") (class "Default")
      (node (ref "D9") (pin "1") (pinfunction "1_1") (pintype "passive"))
    )
    (net (code "128") (name "unconnected-(D14-Pad1)") (class "Default")
      (node (ref "D14") (pin "1") (pinfunction "1_1") (pintype "passive"))
    )
    (net (code "129") (name "unconnected-(H1-Pad1)") (class "Default")
      (node (ref "H1") (pin "1") (pinfunction "1_1") (pintype "power_in+no_connect"))
    )
    (net (code "130") (name "unconnected-(H2-Pad1)") (class "Default")
      (node (ref "H2") (pin "1") (pinfunction "1_1") (pintype "power_in+no_connect"))
    )
    (net (code "131") (name "unconnected-(H3-Pad1)") (class "Default")
      (node (ref "H3") (pin "1") (pinfunction "1_1") (pintype "power_in+no_connect"))
    )
    (net (code "132") (name "unconnected-(H4-Pad1)") (class "Default")
      (node (ref "H4") (pin "1") (pinfunction "1_1") (pintype "power_in+no_connect"))
    )
    (net (code "133") (name "unconnected-(U2-Pad1)") (class "Default")
      (node (ref "U2") (pin "1") (pintype "passive"))
    )
    (net (code "134") (name "unconnected-(U2-Pad4)") (class "Default")
      (node (ref "U2") (pin "4") (pintype "passive"))
    )
    (net (code "135") (name "unconnected-(U5-Pad1)") (class "Default")
      (node (ref "U5") (pin "1") (pintype "passive"))
    )
    (net (code "136") (name "unconnected-(U5-Pad4)") (class "Default")
      (node (ref "U5") (pin "4") (pintype "passive"))
    )
  )
)
